# Main_Power.net
KiCad netlist of a schematic drawn in Altium Designer
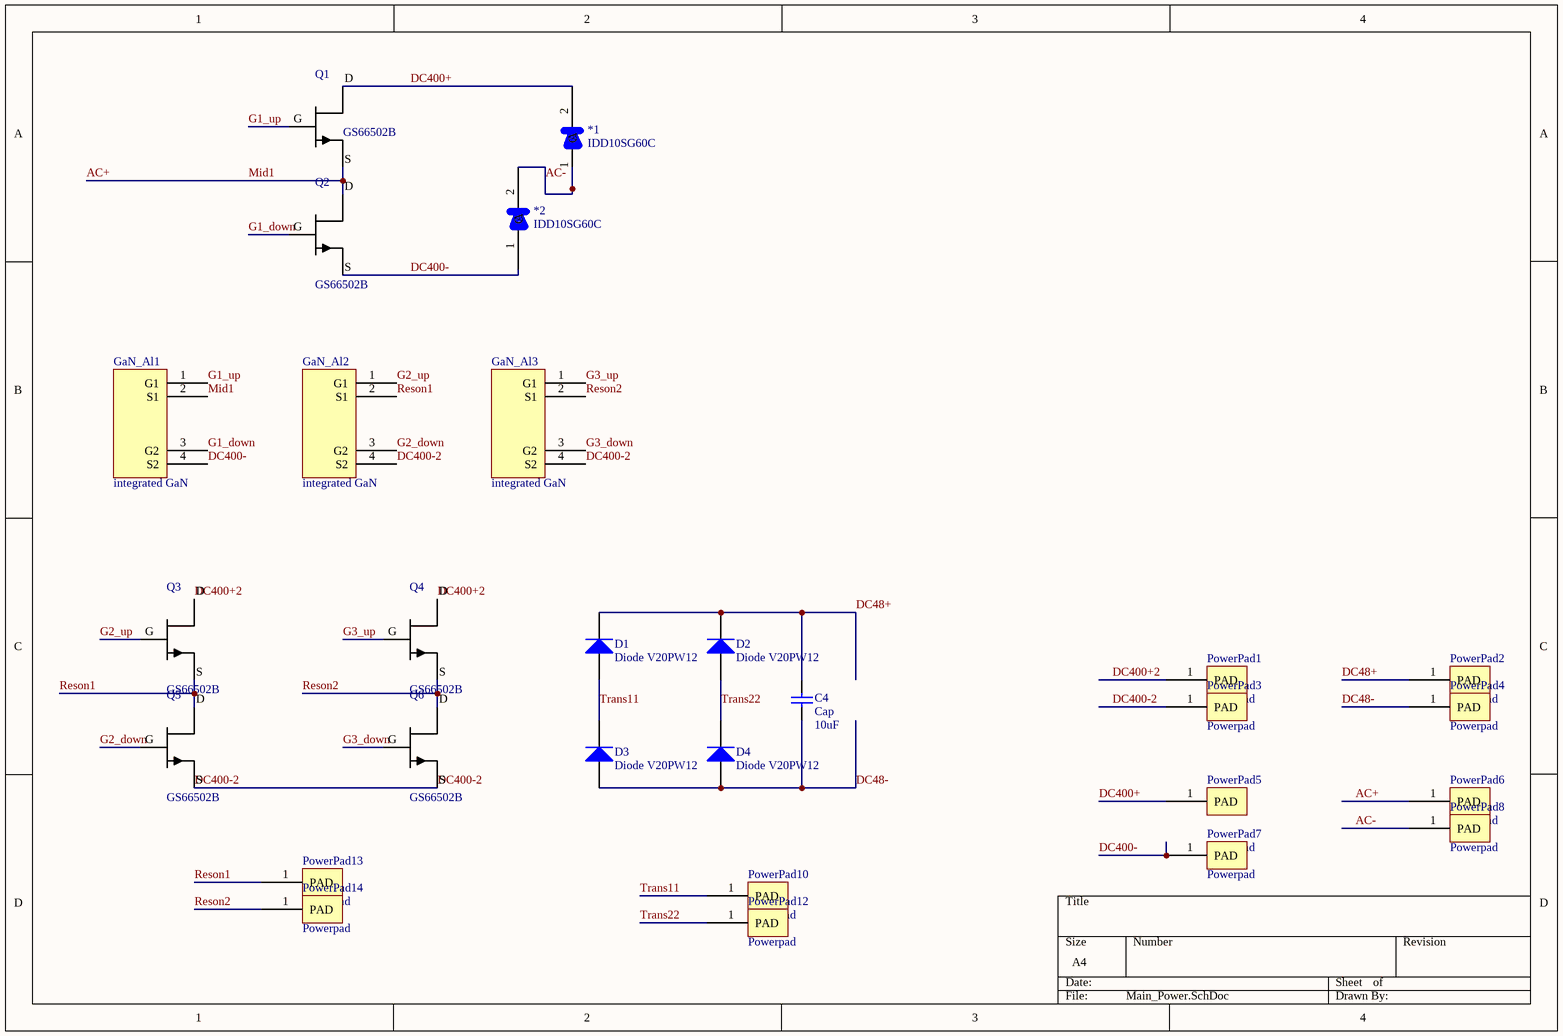
[diagram p0: Main_Power.SchDoc]

(export (version "E")
  (design (tool "Eeschema 10.0.6"))
  (components
    (comp (ref "*1")
      (value "IDD10SG60C")
      (footprint "IDD10SG60C")
      (libsource (lib "Lib_lhy - 副本") (part "IDD10SG60C"))
    )
    (comp (ref "*2")
      (value "IDD10SG60C")
      (footprint "IDD10SG60C")
      (libsource (lib "Lib_lhy - 副本") (part "IDD10SG60C"))
    )
    (comp (ref "C4")
      (value "Cap")
      (footprint "C_Al")
      (description "Capacitor")
      (fields (field (name "ALTIUM_VALUE") "10uF") (field (name "PUBLISHER") "Altium Limited"))
      (libsource (lib "Miscellaneous Devices") (part "Cap"))
    )
    (comp (ref "D1")
      (value "Diode V20PW12")
      (footprint "RFN20")
      (description "Default Diode")
      (fields (field (name "PUBLISHER") "Altium Limited"))
      (libsource (lib "Miscellaneous Devices") (part "Diode"))
    )
    (comp (ref "D2")
      (value "Diode V20PW12")
      (footprint "RFN20")
      (description "Default Diode")
      (fields (field (name "PUBLISHER") "Altium Limited"))
      (libsource (lib "Miscellaneous Devices") (part "Diode"))
    )
    (comp (ref "D3")
      (value "Diode V20PW12")
      (footprint "RFN20")
      (description "Default Diode")
      (fields (field (name "PUBLISHER") "Altium Limited"))
      (libsource (lib "Miscellaneous Devices") (part "Diode"))
    )
    (comp (ref "D4")
      (value "Diode V20PW12")
      (footprint "RFN20")
      (description "Default Diode")
      (fields (field (name "PUBLISHER") "Altium Limited"))
      (libsource (lib "Miscellaneous Devices") (part "Diode"))
    )
    (comp (ref "GaN_Al1")
      (value "integrated GaN")
      (footprint "GaN_driver")
      (libsource (lib "Lib_lhy - 副本") (part "GaN_Al"))
    )
    (comp (ref "GaN_Al2")
      (value "integrated GaN")
      (footprint "GaN_driver")
      (libsource (lib "Lib_lhy - 副本") (part "GaN_Al"))
    )
    (comp (ref "GaN_Al3")
      (value "integrated GaN")
      (footprint "GaN_driver")
      (libsource (lib "Lib_lhy - 副本") (part "GaN_Al"))
    )
    (comp (ref "PowerPad1")
      (value "Powerpad")
      (footprint "POWERPAD")
      (libsource (lib "Lib_lhy - 副本") (part "Powerpad"))
    )
    (comp (ref "PowerPad2")
      (value "Powerpad")
      (footprint "POWERPAD")
      (libsource (lib "Lib_lhy - 副本") (part "Powerpad"))
    )
    (comp (ref "PowerPad3")
      (value "Powerpad")
      (footprint "POWERPAD")
      (libsource (lib "Lib_lhy - 副本") (part "Powerpad"))
    )
    (comp (ref "PowerPad4")
      (value "Powerpad")
      (footprint "POWERPAD")
      (libsource (lib "Lib_lhy - 副本") (part "Powerpad"))
    )
    (comp (ref "PowerPad5")
      (value "Powerpad")
      (footprint "POWERPAD")
      (libsource (lib "Lib_lhy - 副本") (part "Powerpad"))
    )
    (comp (ref "PowerPad6")
      (value "Powerpad")
      (footprint "POWERPAD")
      (libsource (lib "Lib_lhy - 副本") (part "Powerpad"))
    )
    (comp (ref "PowerPad7")
      (value "Powerpad")
      (footprint "POWERPAD")
      (libsource (lib "Lib_lhy - 副本") (part "Powerpad"))
    )
    (comp (ref "PowerPad8")
      (value "Powerpad")
      (footprint "POWERPAD")
      (libsource (lib "Lib_lhy - 副本") (part "Powerpad"))
    )
    (comp (ref "PowerPad10")
      (value "Powerpad")
      (footprint "POWERPAD")
      (libsource (lib "Lib_lhy - 副本") (part "Powerpad"))
    )
    (comp (ref "PowerPad12")
      (value "Powerpad")
      (footprint "POWERPAD")
      (libsource (lib "Lib_lhy - 副本") (part "Powerpad"))
    )
    (comp (ref "PowerPad13")
      (value "Powerpad")
      (footprint "POWERPAD")
      (libsource (lib "Lib_lhy - 副本") (part "Powerpad"))
    )
    (comp (ref "PowerPad14")
      (value "Powerpad")
      (footprint "POWERPAD")
      (libsource (lib "Lib_lhy - 副本") (part "Powerpad"))
    )
    (comp (ref "Q1")
      (value "GS66502B")
      (footprint "GS66502B")
      (description "GAN TRANS E-MODE 650V")
      (libsource (lib "GANSYS_ALTIUM_SYMBOL_RELEASE_20170105") (part "GS66502B"))
    )
    (comp (ref "Q2")
      (value "GS66502B")
      (footprint "GS66502B")
      (description "GAN TRANS E-MODE 650V")
      (libsource (lib "GANSYS_ALTIUM_SYMBOL_RELEASE_20170105") (part "GS66502B"))
    )
    (comp (ref "Q3")
      (value "GS66502B")
      (footprint "GS66502B")
      (description "GAN TRANS E-MODE 650V")
      (libsource (lib "GANSYS_ALTIUM_SYMBOL_RELEASE_20170105") (part "GS66502B"))
    )
    (comp (ref "Q4")
      (value "GS66502B")
      (footprint "GS66502B")
      (description "GAN TRANS E-MODE 650V")
      (libsource (lib "GANSYS_ALTIUM_SYMBOL_RELEASE_20170105") (part "GS66502B"))
    )
    (comp (ref "Q5")
      (value "GS66502B")
      (footprint "GS66502B")
      (description "GAN TRANS E-MODE 650V")
      (libsource (lib "GANSYS_ALTIUM_SYMBOL_RELEASE_20170105") (part "GS66502B"))
    )
    (comp (ref "Q6")
      (value "GS66502B")
      (footprint "GS66502B")
      (description "GAN TRANS E-MODE 650V")
      (libsource (lib "GANSYS_ALTIUM_SYMBOL_RELEASE_20170105") (part "GS66502B"))
    )
  )
  (nets
    (net (code "1") (name "/AC+") (class "Default")
      (node (ref "GaN_Al1") (pin "2") (pinfunction "S1_2") (pintype "passive"))
      (node (ref "PowerPad6") (pin "1") (pinfunction "PAD_1") (pintype "passive"))
      (node (ref "Q1") (pin "S") (pinfunction "S_S") (pintype "passive"))
      (node (ref "Q2") (pin "D") (pinfunction "D_D") (pintype "passive"))
    )
    (net (code "2") (name "/AC-") (class "Default")
      (node (ref "*1") (pin "1") (pinfunction "A_1") (pintype "passive"))
      (node (ref "*2") (pin "2") (pinfunction "C_2") (pintype "passive"))
      (node (ref "PowerPad8") (pin "1") (pinfunction "PAD_1") (pintype "passive"))
    )
    (net (code "3") (name "/DC48+") (class "Default")
      (node (ref "C4") (pin "1") (pinfunction "1_1") (pintype "passive"))
      (node (ref "D1") (pin "2") (pinfunction "K_2") (pintype "passive"))
      (node (ref "D2") (pin "2") (pinfunction "K_2") (pintype "passive"))
      (node (ref "PowerPad2") (pin "1") (pinfunction "PAD_1") (pintype "passive"))
    )
    (net (code "4") (name "/DC48-") (class "Default")
      (node (ref "C4") (pin "2") (pinfunction "2_2") (pintype "passive"))
      (node (ref "D3") (pin "1") (pinfunction "A_1") (pintype "passive"))
      (node (ref "D4") (pin "1") (pinfunction "A_1") (pintype "passive"))
      (node (ref "PowerPad4") (pin "1") (pinfunction "PAD_1") (pintype "passive"))
    )
    (net (code "5") (name "/DC400+") (class "Default")
      (node (ref "*1") (pin "2") (pinfunction "C_2") (pintype "passive"))
      (node (ref "PowerPad5") (pin "1") (pinfunction "PAD_1") (pintype "passive"))
      (node (ref "Q1") (pin "D") (pinfunction "D_D") (pintype "passive"))
    )
    (net (code "6") (name "/DC400+2") (class "Default")
      (node (ref "PowerPad1") (pin "1") (pinfunction "PAD_1") (pintype "passive"))
      (node (ref "Q3") (pin "D") (pinfunction "D_D") (pintype "passive"))
      (node (ref "Q4") (pin "D") (pinfunction "D_D") (pintype "passive"))
    )
    (net (code "7") (name "/DC400-") (class "Default")
      (node (ref "*2") (pin "1") (pinfunction "A_1") (pintype "passive"))
      (node (ref "GaN_Al1") (pin "4") (pinfunction "S2_4") (pintype "passive"))
      (node (ref "PowerPad7") (pin "1") (pinfunction "PAD_1") (pintype "passive"))
      (node (ref "Q2") (pin "S") (pinfunction "S_S") (pintype "passive"))
    )
    (net (code "8") (name "/DC400-2") (class "Default")
      (node (ref "GaN_Al2") (pin "4") (pinfunction "S2_4") (pintype "passive"))
      (node (ref "GaN_Al3") (pin "4") (pinfunction "S2_4") (pintype "passive"))
      (node (ref "PowerPad3") (pin "1") (pinfunction "PAD_1") (pintype "passive"))
      (node (ref "Q5") (pin "S") (pinfunction "S_S") (pintype "passive"))
      (node (ref "Q6") (pin "S") (pinfunction "S_S") (pintype "passive"))
    )
    (net (code "9") (name "/G1_down") (class "Default")
      (node (ref "GaN_Al1") (pin "3") (pinfunction "G2_3") (pintype "passive"))
      (node (ref "Q2") (pin "G") (pinfunction "G_G") (pintype "passive"))
    )
    (net (code "10") (name "/G1_up") (class "Default")
      (node (ref "GaN_Al1") (pin "1") (pinfunction "G1_1") (pintype "passive"))
      (node (ref "Q1") (pin "G") (pinfunction "G_G") (pintype "passive"))
    )
    (net (code "11") (name "/G2_down") (class "Default")
      (node (ref "GaN_Al2") (pin "3") (pinfunction "G2_3") (pintype "passive"))
      (node (ref "Q5") (pin "G") (pinfunction "G_G") (pintype "passive"))
    )
    (net (code "12") (name "/G2_up") (class "Default")
      (node (ref "GaN_Al2") (pin "1") (pinfunction "G1_1") (pintype "passive"))
      (node (ref "Q3") (pin "G") (pinfunction "G_G") (pintype "passive"))
    )
    (net (code "13") (name "/G3_down") (class "Default")
      (node (ref "GaN_Al3") (pin "3") (pinfunction "G2_3") (pintype "passive"))
      (node (ref "Q6") (pin "G") (pinfunction "G_G") (pintype "passive"))
    )
    (net (code "14") (name "/G3_up") (class "Default")
      (node (ref "GaN_Al3") (pin "1") (pinfunction "G1_1") (pintype "passive"))
      (node (ref "Q4") (pin "G") (pinfunction "G_G") (pintype "passive"))
    )
    (net (code "15") (name "/Reson1") (class "Default")
      (node (ref "GaN_Al2") (pin "2") (pinfunction "S1_2") (pintype "passive"))
      (node (ref "PowerPad13") (pin "1") (pinfunction "PAD_1") (pintype "passive"))
      (node (ref "Q3") (pin "S") (pinfunction "S_S") (pintype "passive"))
      (node (ref "Q5") (pin "D") (pinfunction "D_D") (pintype "passive"))
    )
    (net (code "16") (name "/Reson2") (class "Default")
      (node (ref "GaN_Al3") (pin "2") (pinfunction "S1_2") (pintype "passive"))
      (node (ref "PowerPad14") (pin "1") (pinfunction "PAD_1") (pintype "passive"))
      (node (ref "Q4") (pin "S") (pinfunction "S_S") (pintype "passive"))
      (node (ref "Q6") (pin "D") (pinfunction "D_D") (pintype "passive"))
    )
    (net (code "17") (name "/Trans11") (class "Default")
      (node (ref "D1") (pin "1") (pinfunction "A_1") (pintype "passive"))
      (node (ref "D3") (pin "2") (pinfunction "K_2") (pintype "passive"))
      (node (ref "PowerPad10") (pin "1") (pinfunction "PAD_1") (pintype "passive"))
    )
    (net (code "18") (name "/Trans22") (class "Default")
      (node (ref "D2") (pin "1") (pinfunction "A_1") (pintype "passive"))
      (node (ref "D4") (pin "2") (pinfunction "K_2") (pintype "passive"))
      (node (ref "PowerPad12") (pin "1") (pinfunction "PAD_1") (pintype "passive"))
    )
  )
)
